# robot_balance.net
KiCad netlist of a schematic drawn in EAGLE
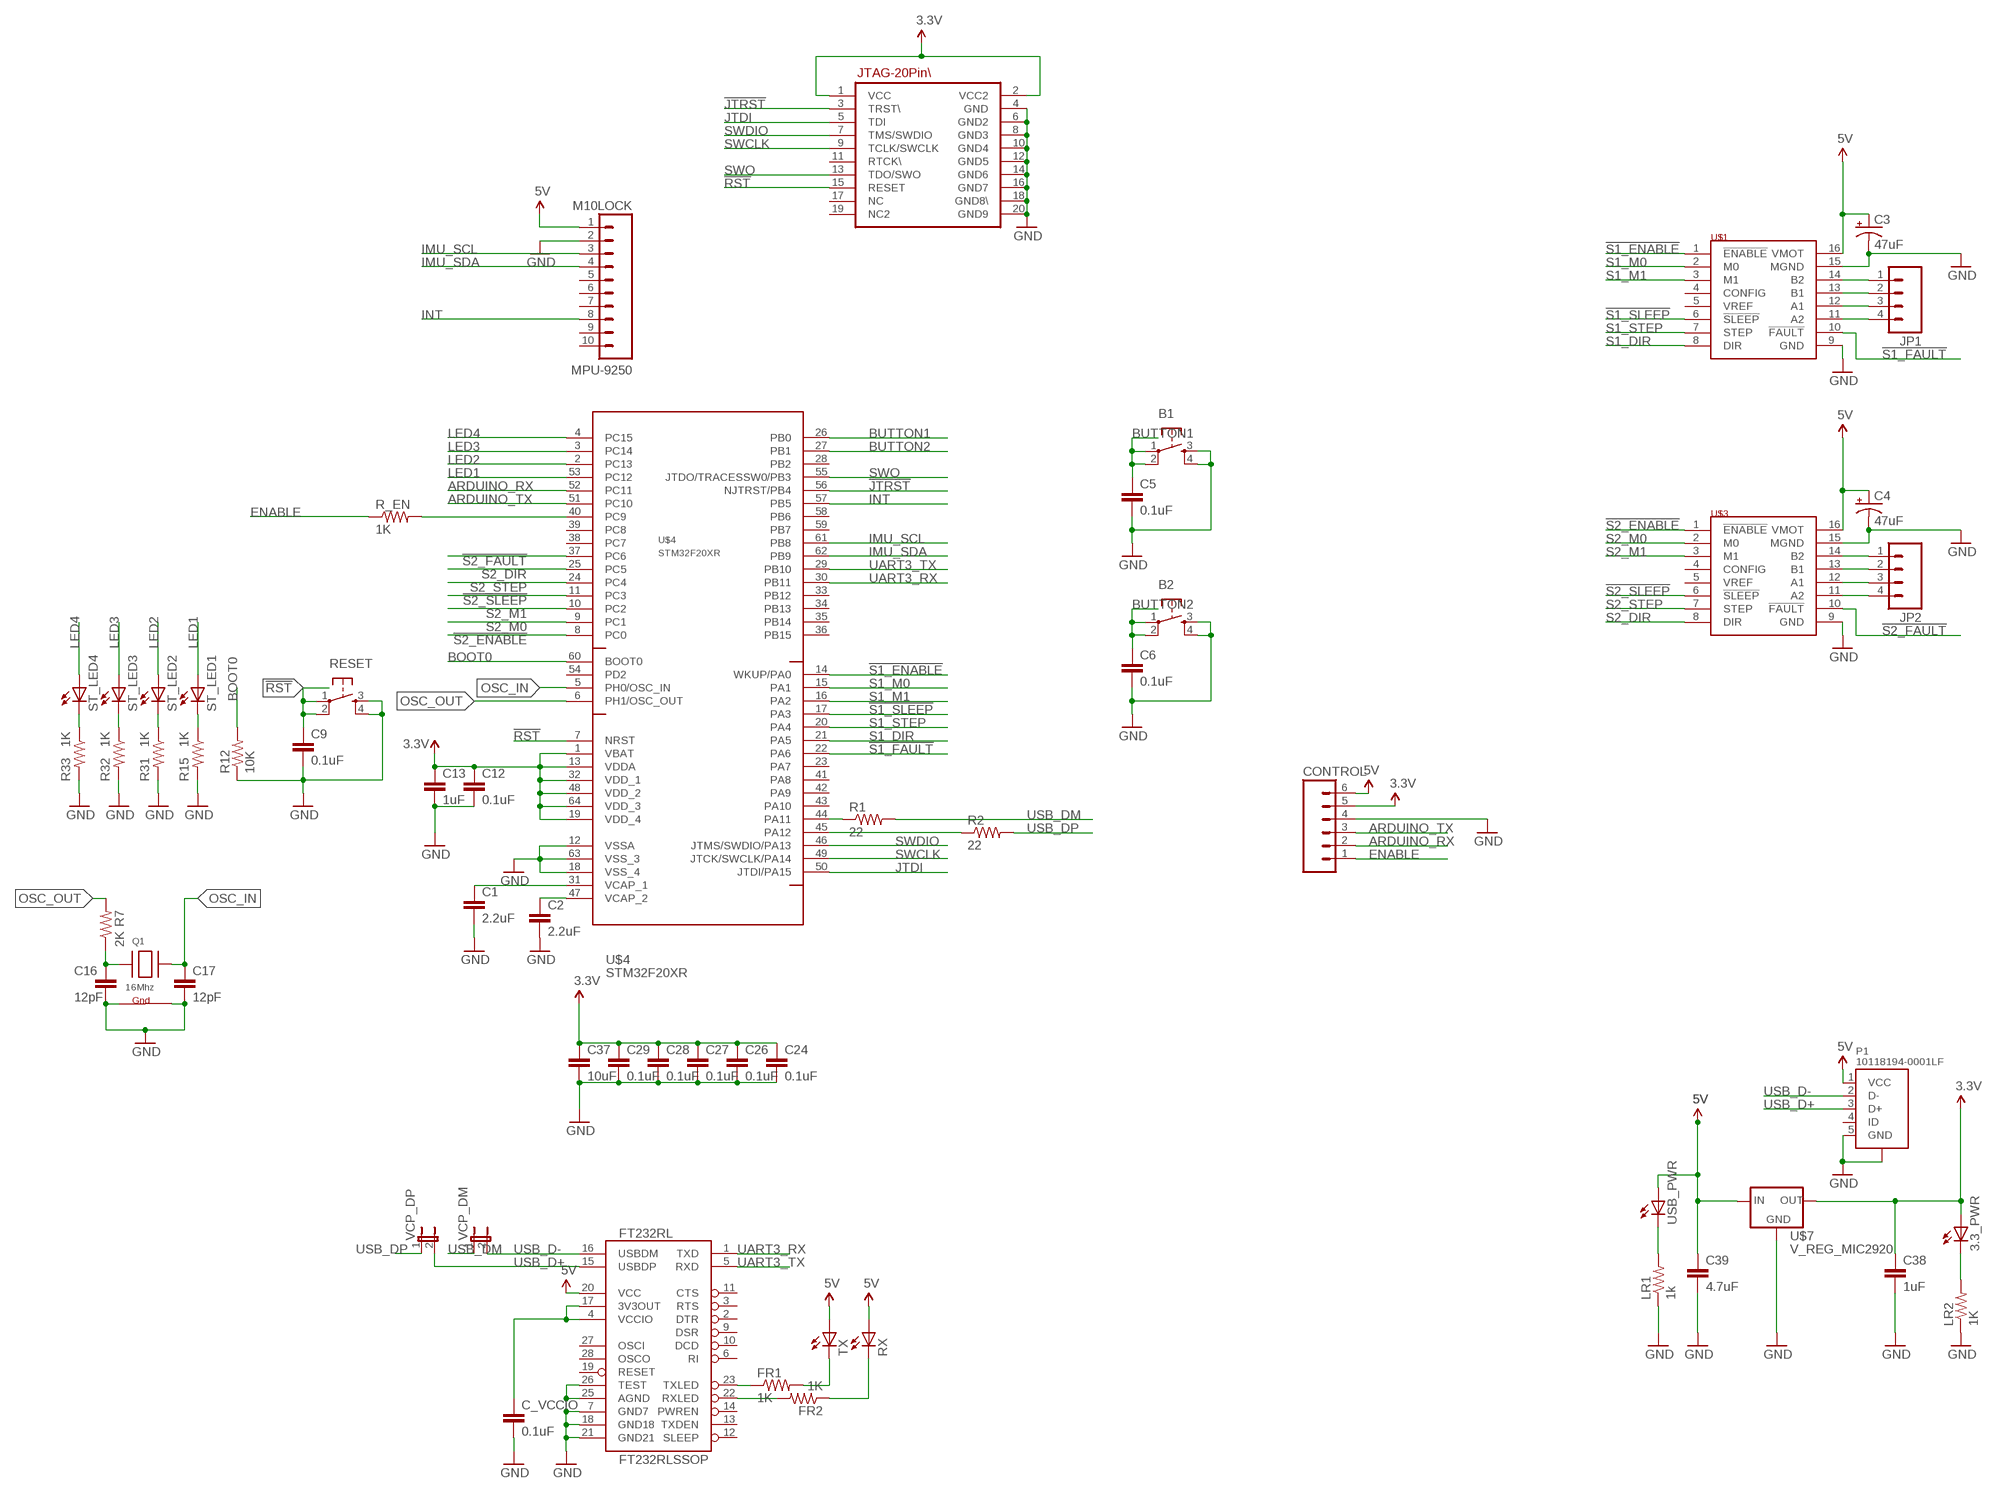
[diagram p0: schematic, sheet 1]

(export (version "E")
  (design (tool "Eeschema 10.0.6"))
  (components
    (comp (ref "3.3_PWR")
      (value "LEDCHIPLED_0805")
      (footprint "eagle-import:CHIPLED_0805")
      (libsource (lib "eagle-import") (part "LEDCHIPLED_0805"))
    )
    (comp (ref "B1")
      (value "TAC_SWITCHSMD")
      (footprint "eagle-import:TACTILE-SWITCH-SMD")
      (libsource (lib "eagle-import") (part "TAC_SWITCHSMD"))
    )
    (comp (ref "B2")
      (value "TAC_SWITCHSMD")
      (footprint "eagle-import:TACTILE-SWITCH-SMD")
      (libsource (lib "eagle-import") (part "TAC_SWITCHSMD"))
    )
    (comp (ref "C1")
      (value "2.2uF")
      (footprint "eagle-import:0805")
      (libsource (lib "eagle-import") (part "2.2UF-25V-+80/-20(0805)"))
    )
    (comp (ref "C2")
      (value "2.2uF")
      (footprint "eagle-import:0805")
      (libsource (lib "eagle-import") (part "2.2UF-25V-+80/-20(0805)"))
    )
    (comp (ref "C3")
      (value "47uF")
      (footprint "eagle-import:EIA3528")
      (libsource (lib "eagle-import") (part "47UF-10V-10%(TANT)"))
    )
    (comp (ref "C4")
      (value "47uF")
      (footprint "eagle-import:EIA3528")
      (libsource (lib "eagle-import") (part "47UF-10V-10%(TANT)"))
    )
    (comp (ref "C5")
      (value "0.1uF")
      (footprint "eagle-import:0805")
      (libsource (lib "eagle-import") (part "2.2UF-25V-+80/-20(0805)"))
    )
    (comp (ref "C6")
      (value "0.1uF")
      (footprint "eagle-import:0805")
      (libsource (lib "eagle-import") (part "2.2UF-25V-+80/-20(0805)"))
    )
    (comp (ref "C9")
      (value "0.1uF")
      (footprint "eagle-import:0805")
      (libsource (lib "eagle-import") (part "2.2UF-25V-+80/-20(0805)"))
    )
    (comp (ref "C12")
      (value "0.1uF")
      (footprint "eagle-import:0805")
      (libsource (lib "eagle-import") (part "2.2UF-25V-+80/-20(0805)"))
    )
    (comp (ref "C13")
      (value "1uF")
      (footprint "eagle-import:0805")
      (libsource (lib "eagle-import") (part "2.2UF-25V-+80/-20(0805)"))
    )
    (comp (ref "C16")
      (value "12pF")
      (footprint "eagle-import:0805")
      (libsource (lib "eagle-import") (part "CAP0805"))
    )
    (comp (ref "C17")
      (value "12pF")
      (footprint "eagle-import:0805")
      (libsource (lib "eagle-import") (part "CAP0805"))
    )
    (comp (ref "C24")
      (value "0.1uF")
      (footprint "eagle-import:0805")
      (libsource (lib "eagle-import") (part "2.2UF-25V-+80/-20(0805)"))
    )
    (comp (ref "C26")
      (value "0.1uF")
      (footprint "eagle-import:0805")
      (libsource (lib "eagle-import") (part "2.2UF-25V-+80/-20(0805)"))
    )
    (comp (ref "C27")
      (value "0.1uF")
      (footprint "eagle-import:0805")
      (libsource (lib "eagle-import") (part "2.2UF-25V-+80/-20(0805)"))
    )
    (comp (ref "C28")
      (value "0.1uF")
      (footprint "eagle-import:0805")
      (libsource (lib "eagle-import") (part "2.2UF-25V-+80/-20(0805)"))
    )
    (comp (ref "C29")
      (value "0.1uF")
      (footprint "eagle-import:0805")
      (libsource (lib "eagle-import") (part "2.2UF-25V-+80/-20(0805)"))
    )
    (comp (ref "C37")
      (value "10uF")
      (footprint "eagle-import:0805")
      (libsource (lib "eagle-import") (part "2.2UF-25V-+80/-20(0805)"))
    )
    (comp (ref "C38")
      (value "1uF")
      (footprint "eagle-import:0805")
      (libsource (lib "eagle-import") (part "22UF-6.3V-20%(0805)"))
    )
    (comp (ref "C39")
      (value "4.7uF")
      (footprint "eagle-import:0805")
      (libsource (lib "eagle-import") (part "22UF-6.3V-20%(0805)"))
    )
    (comp (ref "CONTROL")
      (value "M06POLAR_LOCK")
      (footprint "eagle-import:MOLEX-1X6_LOCK")
      (libsource (lib "eagle-import") (part "M06POLAR_LOCK"))
    )
    (comp (ref "C_VCCIO")
      (value "0.1uF")
      (footprint "eagle-import:0603-CAP")
      (libsource (lib "eagle-import") (part "CAP0603-CAP"))
    )
    (comp (ref "FR1")
      (value "1K")
      (footprint "eagle-import:0603-RES")
      (libsource (lib "eagle-import") (part "RESISTOR0603-RES"))
    )
    (comp (ref "FR2")
      (value "1K")
      (footprint "eagle-import:0603-RES")
      (libsource (lib "eagle-import") (part "RESISTOR0603-RES"))
    )
    (comp (ref "FT232RL")
      (value "FT232RLSSOP")
      (footprint "eagle-import:SSOP28DB")
      (libsource (lib "eagle-import") (part "FT232RLSSOP"))
    )
    (comp (ref "JP1")
      (value "M04POLAR_LOCK")
      (footprint "eagle-import:MOLEX-1X4_LOCK")
      (libsource (lib "eagle-import") (part "M04POLAR_LOCK"))
    )
    (comp (ref "JP2")
      (value "M04POLAR_LOCK")
      (footprint "eagle-import:MOLEX-1X4_LOCK")
      (libsource (lib "eagle-import") (part "M04POLAR_LOCK"))
    )
    (comp (ref "LR1")
      (value "1k")
      (footprint "eagle-import:0805")
      (libsource (lib "eagle-import") (part "SparkFun-Resistors_RESISTOR0805-RES"))
    )
    (comp (ref "LR2")
      (value "1K")
      (footprint "eagle-import:0805")
      (libsource (lib "eagle-import") (part "SparkFun-Resistors_RESISTOR0805-RES"))
    )
    (comp (ref "MPU-9250")
      (value "M10LOCK")
      (footprint "eagle-import:1X10_LOCK")
      (libsource (lib "eagle-import") (part "M10LOCK"))
    )
    (comp (ref "P1")
      (value "10118194-0001LF")
      (footprint "eagle-import:10118194-0001LF")
      (fields
        (field (name "DISTPARTNO") "609-4618-1-ND")
        (field (name "MANUFACTURER") "FCI")
        (field (name "PARTNO") "GT10040")
      )
      (libsource (lib "eagle-import") (part "10118194-0001LF"))
    )
    (comp (ref "Q1")
      (value "16Mhz")
      (footprint "eagle-import:NX3225")
      (libsource (lib "eagle-import") (part "XTAL-4-3225"))
    )
    (comp (ref "R1")
      (value "22")
      (footprint "eagle-import:0805")
      (libsource (lib "eagle-import") (part "RESISTOR0805-RES"))
    )
    (comp (ref "R2")
      (value "22")
      (footprint "eagle-import:0805")
      (libsource (lib "eagle-import") (part "RESISTOR0805-RES"))
    )
    (comp (ref "R7")
      (value "2K")
      (footprint "eagle-import:0805")
      (libsource (lib "eagle-import") (part "SparkFun-Resistors_RESISTOR0805-RES"))
    )
    (comp (ref "R12")
      (value "10K")
      (footprint "eagle-import:0805")
      (libsource (lib "eagle-import") (part "RESISTOR0805-RES"))
    )
    (comp (ref "R15")
      (value "1K")
      (footprint "eagle-import:0805")
      (libsource (lib "eagle-import") (part "SparkFun-Resistors_RESISTOR0805-RES"))
    )
    (comp (ref "R31")
      (value "1K")
      (footprint "eagle-import:0805")
      (libsource (lib "eagle-import") (part "SparkFun-Resistors_RESISTOR0805-RES"))
    )
    (comp (ref "R32")
      (value "1K")
      (footprint "eagle-import:0805")
      (libsource (lib "eagle-import") (part "SparkFun-Resistors_RESISTOR0805-RES"))
    )
    (comp (ref "R33")
      (value "1K")
      (footprint "eagle-import:0805")
      (libsource (lib "eagle-import") (part "SparkFun-Resistors_RESISTOR0805-RES"))
    )
    (comp (ref "RESET")
      (value "TAC_SWITCHSMD")
      (footprint "eagle-import:TACTILE-SWITCH-SMD")
      (libsource (lib "eagle-import") (part "TAC_SWITCHSMD"))
    )
    (comp (ref "RX")
      (value "LEDCHIPLED_0805")
      (footprint "eagle-import:CHIPLED_0805")
      (libsource (lib "eagle-import") (part "LEDCHIPLED_0805"))
    )
    (comp (ref "R_EN")
      (value "1K")
      (footprint "eagle-import:0603-RES")
      (libsource (lib "eagle-import") (part "RESISTOR0603-RES"))
    )
    (comp (ref "ST_LED1")
      (value "LEDCHIPLED_0805")
      (footprint "eagle-import:CHIPLED_0805")
      (libsource (lib "eagle-import") (part "LEDCHIPLED_0805"))
    )
    (comp (ref "ST_LED2")
      (value "LEDCHIPLED_0805")
      (footprint "eagle-import:CHIPLED_0805")
      (libsource (lib "eagle-import") (part "LEDCHIPLED_0805"))
    )
    (comp (ref "ST_LED3")
      (value "LEDCHIPLED_0805")
      (footprint "eagle-import:CHIPLED_0805")
      (libsource (lib "eagle-import") (part "LEDCHIPLED_0805"))
    )
    (comp (ref "ST_LED4")
      (value "LEDCHIPLED_0805")
      (footprint "eagle-import:CHIPLED_0805")
      (libsource (lib "eagle-import") (part "LEDCHIPLED_0805"))
    )
    (comp (ref "TX")
      (value "LEDCHIPLED_0805")
      (footprint "eagle-import:CHIPLED_0805")
      (libsource (lib "eagle-import") (part "LEDCHIPLED_0805"))
    )
    (comp (ref "U$1")
      (value "POLOLU_DRV8834")
      (footprint "eagle-import:POLOLU_DRV8834")
      (libsource (lib "eagle-import") (part "POLOLU_DRV8834"))
    )
    (comp (ref "U$2")
      (value "JTAG_20PIN")
      (footprint "eagle-import:2X10")
      (libsource (lib "eagle-import") (part "JTAG_20PIN"))
    )
    (comp (ref "U$3")
      (value "POLOLU_DRV8834")
      (footprint "eagle-import:POLOLU_DRV8834")
      (libsource (lib "eagle-import") (part "POLOLU_DRV8834"))
    )
    (comp (ref "U$4")
      (value "STM32F20XR")
      (footprint "eagle-import:LQFP64")
      (libsource (lib "eagle-import") (part "STM32F20XR"))
    )
    (comp (ref "U$7")
      (value "V_REG_MIC2920")
      (footprint "eagle-import:SOT223")
      (libsource (lib "eagle-import") (part "V_REG_MIC2920"))
    )
    (comp (ref "USB_PWR")
      (value "LEDCHIP-LED0805")
      (footprint "eagle-import:CHIP-LED0805")
      (libsource (lib "eagle-import") (part "LEDCHIP-LED0805"))
    )
    (comp (ref "VCP_DM")
      (value "JUMPER-2SMD-NO")
      (footprint "eagle-import:SJ_2S-NO")
      (libsource (lib "eagle-import") (part "JUMPER-2SMD-NO"))
    )
    (comp (ref "VCP_DP")
      (value "JUMPER-2SMD-NO")
      (footprint "eagle-import:SJ_2S-NO")
      (libsource (lib "eagle-import") (part "JUMPER-2SMD-NO"))
    )
  )
  (nets
    (net (code "1") (name "/ARDUINO_RX") (class "Default")
      (node (ref "CONTROL") (pin "2") (pinfunction "2_2") (pintype "passive"))
      (node (ref "U$4") (pin "52") (pinfunction "PC11_52") (pintype "bidirectional"))
    )
    (net (code "2") (name "/ARDUINO_TX") (class "Default")
      (node (ref "CONTROL") (pin "3") (pinfunction "3_3") (pintype "passive"))
      (node (ref "U$4") (pin "51") (pinfunction "PC10_51") (pintype "bidirectional"))
    )
    (net (code "3") (name "/BOOT0") (class "Default")
      (node (ref "R12") (pin "2") (pinfunction "2_2") (pintype "passive"))
      (node (ref "U$4") (pin "60") (pinfunction "BOOT0_60") (pintype "bidirectional"))
    )
    (net (code "4") (name "/BUTTON1") (class "Default")
      (node (ref "B1") (pin "1") (pinfunction "1_1") (pintype "passive"))
      (node (ref "B1") (pin "2") (pinfunction "2_2") (pintype "passive"))
      (node (ref "C5") (pin "1") (pinfunction "1_1") (pintype "passive"))
      (node (ref "U$4") (pin "26") (pinfunction "PB0_26") (pintype "bidirectional"))
    )
    (net (code "5") (name "/BUTTON2") (class "Default")
      (node (ref "B2") (pin "1") (pinfunction "1_1") (pintype "passive"))
      (node (ref "B2") (pin "2") (pinfunction "2_2") (pintype "passive"))
      (node (ref "C6") (pin "1") (pinfunction "1_1") (pintype "passive"))
      (node (ref "U$4") (pin "27") (pinfunction "PB1_27") (pintype "bidirectional"))
    )
    (net (code "6") (name "/ENABLE") (class "Default")
      (node (ref "CONTROL") (pin "1") (pinfunction "1_1") (pintype "passive"))
      (node (ref "R_EN") (pin "1") (pinfunction "1_1") (pintype "passive"))
    )
    (net (code "7") (name "/IMU_SCL") (class "Default")
      (node (ref "MPU-9250") (pin "3") (pinfunction "3_3") (pintype "passive"))
      (node (ref "U$4") (pin "61") (pinfunction "PB8_61") (pintype "bidirectional"))
    )
    (net (code "8") (name "/IMU_SDA") (class "Default")
      (node (ref "MPU-9250") (pin "4") (pinfunction "4_4") (pintype "passive"))
      (node (ref "U$4") (pin "62") (pinfunction "PB9_62") (pintype "bidirectional"))
    )
    (net (code "9") (name "/INT") (class "Default")
      (node (ref "MPU-9250") (pin "8") (pinfunction "8_8") (pintype "passive"))
      (node (ref "U$4") (pin "57") (pinfunction "PB5_57") (pintype "bidirectional"))
    )
    (net (code "10") (name "/JTDI") (class "Default")
      (node (ref "U$2") (pin "5") (pinfunction "TDI_5") (pintype "bidirectional"))
      (node (ref "U$4") (pin "50") (pinfunction "JTDI/PA15_50") (pintype "bidirectional"))
    )
    (net (code "11") (name "/LED1") (class "Default")
      (node (ref "ST_LED1") (pin "A") (pinfunction "A_A") (pintype "passive"))
      (node (ref "U$4") (pin "53") (pinfunction "PC12_53") (pintype "bidirectional"))
    )
    (net (code "12") (name "/LED2") (class "Default")
      (node (ref "ST_LED2") (pin "A") (pinfunction "A_A") (pintype "passive"))
      (node (ref "U$4") (pin "2") (pinfunction "PC13_2") (pintype "bidirectional"))
    )
    (net (code "13") (name "/LED3") (class "Default")
      (node (ref "ST_LED3") (pin "A") (pinfunction "A_A") (pintype "passive"))
      (node (ref "U$4") (pin "3") (pinfunction "PC14_3") (pintype "bidirectional"))
    )
    (net (code "14") (name "/LED4") (class "Default")
      (node (ref "ST_LED4") (pin "A") (pinfunction "A_A") (pintype "passive"))
      (node (ref "U$4") (pin "4") (pinfunction "PC15_4") (pintype "bidirectional"))
    )
    (net (code "15") (name "/S1_DIR") (class "Default")
      (node (ref "U$1") (pin "8") (pinfunction "DIR_8") (pintype "bidirectional"))
      (node (ref "U$4") (pin "21") (pinfunction "PA5_21") (pintype "bidirectional"))
    )
    (net (code "16") (name "/S1_M0") (class "Default")
      (node (ref "U$1") (pin "2") (pinfunction "M0_2") (pintype "bidirectional"))
      (node (ref "U$4") (pin "15") (pinfunction "PA1_15") (pintype "bidirectional"))
    )
    (net (code "17") (name "/S1_M1") (class "Default")
      (node (ref "U$1") (pin "3") (pinfunction "M1_3") (pintype "bidirectional"))
      (node (ref "U$4") (pin "16") (pinfunction "PA2_16") (pintype "bidirectional"))
    )
    (net (code "18") (name "/S1_STEP") (class "Default")
      (node (ref "U$1") (pin "7") (pinfunction "STEP_7") (pintype "bidirectional"))
      (node (ref "U$4") (pin "20") (pinfunction "PA4_20") (pintype "bidirectional"))
    )
    (net (code "19") (name "/S2_DIR") (class "Default")
      (node (ref "U$3") (pin "8") (pinfunction "DIR_8") (pintype "bidirectional"))
      (node (ref "U$4") (pin "25") (pinfunction "PC5_25") (pintype "bidirectional"))
    )
    (net (code "20") (name "/S2_M0") (class "Default")
      (node (ref "U$3") (pin "2") (pinfunction "M0_2") (pintype "bidirectional"))
      (node (ref "U$4") (pin "9") (pinfunction "PC1_9") (pintype "bidirectional"))
    )
    (net (code "21") (name "/S2_M1") (class "Default")
      (node (ref "U$3") (pin "3") (pinfunction "M1_3") (pintype "bidirectional"))
      (node (ref "U$4") (pin "10") (pinfunction "PC2_10") (pintype "bidirectional"))
    )
    (net (code "22") (name "/S2_STEP") (class "Default")
      (node (ref "U$3") (pin "7") (pinfunction "STEP_7") (pintype "bidirectional"))
      (node (ref "U$4") (pin "24") (pinfunction "PC4_24") (pintype "bidirectional"))
    )
    (net (code "23") (name "/SWCLK") (class "Default")
      (node (ref "U$2") (pin "9") (pinfunction "TCLK/SWCLK_9") (pintype "bidirectional"))
      (node (ref "U$4") (pin "49") (pinfunction "JTCK/SWCLK/PA14_49") (pintype "bidirectional"))
    )
    (net (code "24") (name "/SWDIO") (class "Default")
      (node (ref "U$2") (pin "7") (pinfunction "TMS/SWDIO_7") (pintype "bidirectional"))
      (node (ref "U$4") (pin "46") (pinfunction "JTMS/SWDIO/PA13_46") (pintype "bidirectional"))
    )
    (net (code "25") (name "/SWO") (class "Default")
      (node (ref "U$2") (pin "13") (pinfunction "TDO/SWO_13") (pintype "bidirectional"))
      (node (ref "U$4") (pin "55") (pinfunction "JTDO/TRACESSW0/PB3_55") (pintype "bidirectional"))
    )
    (net (code "26") (name "/UART3_RX") (class "Default")
      (node (ref "FT232RL") (pin "1") (pinfunction "TXD_1") (pintype "output"))
      (node (ref "U$4") (pin "30") (pinfunction "PB11_30") (pintype "bidirectional"))
    )
    (net (code "27") (name "/UART3_TX") (class "Default")
      (node (ref "FT232RL") (pin "5") (pinfunction "RXD_5") (pintype "input"))
      (node (ref "U$4") (pin "29") (pinfunction "PB10_29") (pintype "bidirectional"))
    )
    (net (code "28") (name "/USB_D+") (class "Default")
      (node (ref "FT232RL") (pin "15") (pinfunction "USBDP_15") (pintype "bidirectional"))
      (node (ref "P1") (pin "3") (pinfunction "D+_3") (pintype "passive"))
      (node (ref "VCP_DP") (pin "2") (pinfunction "2_2") (pintype "passive"))
    )
    (net (code "29") (name "/USB_D-") (class "Default")
      (node (ref "FT232RL") (pin "16") (pinfunction "USBDM_16") (pintype "bidirectional"))
      (node (ref "P1") (pin "2") (pinfunction "D-_2") (pintype "passive"))
      (node (ref "VCP_DM") (pin "2") (pinfunction "2_2") (pintype "passive"))
    )
    (net (code "30") (name "/USB_DM") (class "Default")
      (node (ref "R1") (pin "2") (pinfunction "2_2") (pintype "passive"))
      (node (ref "VCP_DM") (pin "1") (pinfunction "1_1") (pintype "passive"))
    )
    (net (code "31") (name "/USB_DP") (class "Default")
      (node (ref "R2") (pin "2") (pinfunction "2_2") (pintype "passive"))
      (node (ref "VCP_DP") (pin "1") (pinfunction "1_1") (pintype "passive"))
    )
    (net (code "32") (name "/~{JTRST}") (class "Default")
      (node (ref "U$2") (pin "3") (pinfunction "TRST\\_3") (pintype "bidirectional"))
      (node (ref "U$4") (pin "56") (pinfunction "NJTRST/PB4_56") (pintype "bidirectional"))
    )
    (net (code "33") (name "/~{RST}") (class "Default")
      (node (ref "C9") (pin "1") (pinfunction "1_1") (pintype "passive"))
      (node (ref "RESET") (pin "1") (pinfunction "1_1") (pintype "passive"))
      (node (ref "RESET") (pin "2") (pinfunction "2_2") (pintype "passive"))
      (node (ref "U$2") (pin "15") (pinfunction "RESET_15") (pintype "bidirectional"))
      (node (ref "U$4") (pin "7") (pinfunction "NRST_7") (pintype "power_in"))
    )
    (net (code "34") (name "/~{S1_ENABLE}") (class "Default")
      (node (ref "U$1") (pin "1") (pinfunction "~{ENABLE}_1") (pintype "bidirectional"))
      (node (ref "U$4") (pin "14") (pinfunction "WKUP/PA0_14") (pintype "bidirectional"))
    )
    (net (code "35") (name "/~{S1_FAULT}") (class "Default")
      (node (ref "U$1") (pin "10") (pinfunction "~{FAULT}_10") (pintype "bidirectional"))
      (node (ref "U$4") (pin "22") (pinfunction "PA6_22") (pintype "bidirectional"))
    )
    (net (code "36") (name "/~{S1_SLEEP}") (class "Default")
      (node (ref "U$1") (pin "6") (pinfunction "~{SLEEP}_6") (pintype "bidirectional"))
      (node (ref "U$4") (pin "17") (pinfunction "PA3_17") (pintype "bidirectional"))
    )
    (net (code "37") (name "/~{S2_ENABLE}") (class "Default")
      (node (ref "U$3") (pin "1") (pinfunction "~{ENABLE}_1") (pintype "bidirectional"))
      (node (ref "U$4") (pin "8") (pinfunction "PC0_8") (pintype "bidirectional"))
    )
    (net (code "38") (name "/~{S2_FAULT}") (class "Default")
      (node (ref "U$3") (pin "10") (pinfunction "~{FAULT}_10") (pintype "bidirectional"))
      (node (ref "U$4") (pin "37") (pinfunction "PC6_37") (pintype "bidirectional"))
    )
    (net (code "39") (name "/~{S2_SLEEP}") (class "Default")
      (node (ref "U$3") (pin "6") (pinfunction "~{SLEEP}_6") (pintype "bidirectional"))
      (node (ref "U$4") (pin "11") (pinfunction "PC3_11") (pintype "bidirectional"))
    )
    (net (code "40") (name "3.3V") (class "Default")
      (node (ref "3.3_PWR") (pin "A") (pinfunction "A_A") (pintype "passive"))
      (node (ref "C12") (pin "1") (pinfunction "1_1") (pintype "passive"))
      (node (ref "C13") (pin "1") (pinfunction "1_1") (pintype "passive"))
      (node (ref "C24") (pin "1") (pinfunction "1_1") (pintype "passive"))
      (node (ref "C26") (pin "1") (pinfunction "1_1") (pintype "passive"))
      (node (ref "C27") (pin "1") (pinfunction "1_1") (pintype "passive"))
      (node (ref "C28") (pin "1") (pinfunction "1_1") (pintype "passive"))
      (node (ref "C29") (pin "1") (pinfunction "1_1") (pintype "passive"))
      (node (ref "C37") (pin "1") (pinfunction "1_1") (pintype "passive"))
      (node (ref "C38") (pin "1") (pinfunction "1_1") (pintype "passive"))
      (node (ref "CONTROL") (pin "5") (pinfunction "5_5") (pintype "passive"))
      (node (ref "U$2") (pin "1") (pinfunction "VCC_1") (pintype "bidirectional"))
      (node (ref "U$2") (pin "2") (pinfunction "VCC2_2") (pintype "bidirectional"))
      (node (ref "U$4") (pin "1") (pinfunction "VBAT_1") (pintype "power_in"))
      (node (ref "U$4") (pin "13") (pinfunction "VDDA_13") (pintype "power_in"))
      (node (ref "U$4") (pin "19") (pinfunction "VDD_4_19") (pintype "power_in"))
      (node (ref "U$4") (pin "32") (pinfunction "VDD_1_32") (pintype "power_in"))
      (node (ref "U$4") (pin "48") (pinfunction "VDD_2_48") (pintype "power_in"))
      (node (ref "U$4") (pin "64") (pinfunction "VDD_3_64") (pintype "power_in"))
      (node (ref "U$7") (pin "3") (pinfunction "OUT_3") (pintype "output"))
    )
    (net (code "41") (name "5V") (class "Default")
      (node (ref "C3") (pin "A") (pinfunction "+_A") (pintype "passive"))
      (node (ref "C39") (pin "1") (pinfunction "1_1") (pintype "passive"))
      (node (ref "C4") (pin "A") (pinfunction "+_A") (pintype "passive"))
      (node (ref "CONTROL") (pin "6") (pinfunction "6_6") (pintype "passive"))
      (node (ref "FT232RL") (pin "20") (pinfunction "VCC_20") (pintype "power_in"))
      (node (ref "MPU-9250") (pin "1") (pinfunction "1_1") (pintype "passive"))
      (node (ref "P1") (pin "1") (pinfunction "VCC_1") (pintype "passive"))
      (node (ref "RX") (pin "A") (pinfunction "A_A") (pintype "passive"))
      (node (ref "TX") (pin "A") (pinfunction "A_A") (pintype "passive"))
      (node (ref "U$1") (pin "16") (pinfunction "VMOT_16") (pintype "power_in"))
      (node (ref "U$3") (pin "16") (pinfunction "VMOT_16") (pintype "power_in"))
      (node (ref "U$7") (pin "1") (pinfunction "IN_1") (pintype "input"))
      (node (ref "USB_PWR") (pin "A") (pinfunction "A_A") (pintype "passive"))
    )
    (net (code "42") (name "GND") (class "Default")
      (node (ref "B1") (pin "3") (pinfunction "3_3") (pintype "passive"))
      (node (ref "B1") (pin "4") (pinfunction "4_4") (pintype "passive"))
      (node (ref "B2") (pin "3") (pinfunction "3_3") (pintype "passive"))
      (node (ref "B2") (pin "4") (pinfunction "4_4") (pintype "passive"))
      (node (ref "C1") (pin "2") (pinfunction "2_2") (pintype "passive"))
      (node (ref "C12") (pin "2") (pinfunction "2_2") (pintype "passive"))
      (node (ref "C13") (pin "2") (pinfunction "2_2") (pintype "passive"))
      (node (ref "C16") (pin "2") (pinfunction "2_2") (pintype "passive"))
      (node (ref "C17") (pin "2") (pinfunction "2_2") (pintype "passive"))
      (node (ref "C2") (pin "2") (pinfunction "2_2") (pintype "passive"))
      (node (ref "C24") (pin "2") (pinfunction "2_2") (pintype "passive"))
      (node (ref "C26") (pin "2") (pinfunction "2_2") (pintype "passive"))
      (node (ref "C27") (pin "2") (pinfunction "2_2") (pintype "passive"))
      (node (ref "C28") (pin "2") (pinfunction "2_2") (pintype "passive"))
      (node (ref "C29") (pin "2") (pinfunction "2_2") (pintype "passive"))
      (node (ref "C3") (pin "C") (pinfunction "-_C") (pintype "passive"))
      (node (ref "C37") (pin "2") (pinfunction "2_2") (pintype "passive"))
      (node (ref "C38") (pin "2") (pinfunction "2_2") (pintype "passive"))
      (node (ref "C39") (pin "2") (pinfunction "2_2") (pintype "passive"))
      (node (ref "C4") (pin "C") (pinfunction "-_C") (pintype "passive"))
      (node (ref "C5") (pin "2") (pinfunction "2_2") (pintype "passive"))
      (node (ref "C6") (pin "2") (pinfunction "2_2") (pintype "passive"))
      (node (ref "C9") (pin "2") (pinfunction "2_2") (pintype "passive"))
      (node (ref "CONTROL") (pin "4") (pinfunction "4_4") (pintype "passive"))
      (node (ref "C_VCCIO") (pin "2") (pinfunction "2_2") (pintype "passive"))
      (node (ref "FT232RL") (pin "18") (pinfunction "GND18_18") (pintype "power_in"))
      (node (ref "FT232RL") (pin "21") (pinfunction "GND21_21") (pintype "power_in"))
      (node (ref "FT232RL") (pin "25") (pinfunction "AGND_25") (pintype "power_in"))
      (node (ref "FT232RL") (pin "26") (pinfunction "TEST_26") (pintype "input"))
      (node (ref "FT232RL") (pin "7") (pinfunction "GND7_7") (pintype "power_in"))
      (node (ref "LR1") (pin "1") (pinfunction "1_1") (pintype "passive"))
      (node (ref "LR2") (pin "1") (pinfunction "1_1") (pintype "passive"))
      (node (ref "MPU-9250") (pin "2") (pinfunction "2_2") (pintype "passive"))
      (node (ref "P1") (pin "5") (pinfunction "GND_5") (pintype "passive"))
      (node (ref "P1") (pin "M1") (pinfunction "SHIELD_M1") (pintype "passive"))
      (node (ref "P1") (pin "M2") (pinfunction "SHIELD_M2") (pintype "passive"))
      (node (ref "P1") (pin "M3") (pinfunction "SHIELD_M3") (pintype "passive"))
      (node (ref "P1") (pin "M4") (pinfunction "SHIELD_M4") (pintype "passive"))
      (node (ref "Q1") (pin "2") (pinfunction "G2_2") (pintype "power_in"))
      (node (ref "Q1") (pin "4") (pinfunction "G1_4") (pintype "power_in"))
      (node (ref "R12") (pin "1") (pinfunction "1_1") (pintype "passive"))
      (node (ref "R15") (pin "2") (pinfunction "2_2") (pintype "passive"))
      (node (ref "R31") (pin "2") (pinfunction "2_2") (pintype "passive"))
      (node (ref "R32") (pin "2") (pinfunction "2_2") (pintype "passive"))
      (node (ref "R33") (pin "2") (pinfunction "2_2") (pintype "passive"))
      (node (ref "RESET") (pin "3") (pinfunction "3_3") (pintype "passive"))
      (node (ref "RESET") (pin "4") (pinfunction "4_4") (pintype "passive"))
      (node (ref "U$1") (pin "15") (pinfunction "MGND_15") (pintype "power_in"))
      (node (ref "U$1") (pin "9") (pinfunction "GND_9") (pintype "power_in"))
      (node (ref "U$2") (pin "10") (pinfunction "GND4_10") (pintype "bidirectional"))
      (node (ref "U$2") (pin "12") (pinfunction "GND5_12") (pintype "bidirectional"))
      (node (ref "U$2") (pin "14") (pinfunction "GND6_14") (pintype "bidirectional"))
      (node (ref "U$2") (pin "16") (pinfunction "GND7_16") (pintype "bidirectional"))
      (node (ref "U$2") (pin "18") (pinfunction "GND8\\_18") (pintype "bidirectional"))
      (node (ref "U$2") (pin "20") (pinfunction "GND9_20") (pintype "bidirectional"))
      (node (ref "U$2") (pin "4") (pinfunction "GND_4") (pintype "bidirectional"))
      (node (ref "U$2") (pin "6") (pinfunction "GND2_6") (pintype "bidirectional"))
      (node (ref "U$2") (pin "8") (pinfunction "GND3_8") (pintype "bidirectional"))
      (node (ref "U$3") (pin "15") (pinfunction "MGND_15") (pintype "power_in"))
      (node (ref "U$3") (pin "9") (pinfunction "GND_9") (pintype "power_in"))
      (node (ref "U$4") (pin "12") (pinfunction "VSSA_12") (pintype "power_in"))
      (node (ref "U$4") (pin "18") (pinfunction "VSS_4_18") (pintype "power_in"))
      (node (ref "U$4") (pin "63") (pinfunction "VSS_3_63") (pintype "power_in"))
      (node (ref "U$7") (pin "2") (pinfunction "GND_2") (pintype "input"))
    )
    (net (code "43") (name "Net-(3.3_PWR-PadC)") (class "Default")
      (node (ref "3.3_PWR") (pin "C") (pinfunction "C_C") (pintype "passive"))
      (node (ref "LR2") (pin "2") (pinfunction "2_2") (pintype "passive"))
    )
    (net (code "44") (name "Net-(FR1-Pad2)") (class "Default")
      (node (ref "FR1") (pin "2") (pinfunction "2_2") (pintype "passive"))
      (node (ref "TX") (pin "C") (pinfunction "C_C") (pintype "passive"))
    )
    (net (code "45") (name "Net-(FR2-Pad1)") (class "Default")
      (node (ref "FR2") (pin "1") (pinfunction "1_1") (pintype "passive"))
      (node (ref "RX") (pin "C") (pinfunction "C_C") (pintype "passive"))
    )
    (net (code "46") (name "Net-(FT232RL-3V3OUT)") (class "Default")
      (node (ref "C_VCCIO") (pin "1") (pinfunction "1_1") (pintype "passive"))
      (node (ref "FT232RL") (pin "17") (pinfunction "3V3OUT_17") (pintype "output"))
      (node (ref "FT232RL") (pin "4") (pinfunction "VCCIO_4") (pintype "power_in"))
    )
    (net (code "47") (name "Net-(FT232RL-RXLED)") (class "Default")
      (node (ref "FR2") (pin "2") (pinfunction "2_2") (pintype "passive"))
      (node (ref "FT232RL") (pin "22") (pinfunction "RXLED_22") (pintype "input"))
    )
    (net (code "48") (name "Net-(FT232RL-TXLED)") (class "Default")
      (node (ref "FR1") (pin "1") (pinfunction "1_1") (pintype "passive"))
      (node (ref "FT232RL") (pin "23") (pinfunction "TXLED_23") (pintype "input"))
    )
    (net (code "49") (name "Net-(LR1-Pad2)") (class "Default")
      (node (ref "LR1") (pin "2") (pinfunction "2_2") (pintype "passive"))
      (node (ref "USB_PWR") (pin "C") (pinfunction "C_C") (pintype "passive"))
    )
    (net (code "50") (name "Net-(Q1-X1)") (class "Default")
      (node (ref "C16") (pin "1") (pinfunction "1_1") (pintype "passive"))
      (node (ref "Q1") (pin "1") (pinfunction "X1_1") (pintype "bidirectional"))
      (node (ref "R7") (pin "1") (pinfunction "1_1") (pintype "passive"))
    )
    (net (code "51") (name "Net-(R15-Pad1)") (class "Default")
      (node (ref "R15") (pin "1") (pinfunction "1_1") (pintype "passive"))
      (node (ref "ST_LED1") (pin "C") (pinfunction "C_C") (pintype "passive"))
    )
    (net (code "52") (name "Net-(R31-Pad1)") (class "Default")
      (node (ref "R31") (pin "1") (pinfunction "1_1") (pintype "passive"))
      (node (ref "ST_LED2") (pin "C") (pinfunction "C_C") (pintype "passive"))
    )
    (net (code "53") (name "Net-(R32-Pad1)") (class "Default")
      (node (ref "R32") (pin "1") (pinfunction "1_1") (pintype "passive"))
      (node (ref "ST_LED3") (pin "C") (pinfunction "C_C") (pintype "passive"))
    )
    (net (code "54") (name "Net-(R33-Pad1)") (class "Default")
      (node (ref "R33") (pin "1") (pinfunction "1_1") (pintype "passive"))
      (node (ref "ST_LED4") (pin "C") (pinfunction "C_C") (pintype "passive"))
    )
    (net (code "55") (name "Net-(U$1-A1)") (class "Default")
      (node (ref "JP1") (pin "3") (pinfunction "3_3") (pintype "passive"))
      (node (ref "U$1") (pin "12") (pinfunction "A1_12") (pintype "bidirectional"))
    )
    (net (code "56") (name "Net-(U$1-A2)") (class "Default")
      (node (ref "JP1") (pin "4") (pinfunction "4_4") (pintype "passive"))
      (node (ref "U$1") (pin "11") (pinfunction "A2_11") (pintype "bidirectional"))
    )
    (net (code "57") (name "Net-(U$1-B1)") (class "Default")
      (node (ref "JP1") (pin "2") (pinfunction "2_2") (pintype "passive"))
      (node (ref "U$1") (pin "13") (pinfunction "B1_13") (pintype "bidirectional"))
    )
    (net (code "58") (name "Net-(U$1-B2)") (class "Default")
      (node (ref "JP1") (pin "1") (pinfunction "1_1") (pintype "passive"))
      (node (ref "U$1") (pin "14") (pinfunction "B2_14") (pintype "bidirectional"))
    )
    (net (code "59") (name "Net-(U$3-A1)") (class "Default")
      (node (ref "JP2") (pin "3") (pinfunction "3_3") (pintype "passive"))
      (node (ref "U$3") (pin "12") (pinfunction "A1_12") (pintype "bidirectional"))
    )
    (net (code "60") (name "Net-(U$3-A2)") (class "Default")
      (node (ref "JP2") (pin "4") (pinfunction "4_4") (pintype "passive"))
      (node (ref "U$3") (pin "11") (pinfunction "A2_11") (pintype "bidirectional"))
    )
    (net (code "61") (name "Net-(U$3-B1)") (class "Default")
      (node (ref "JP2") (pin "2") (pinfunction "2_2") (pintype "passive"))
      (node (ref "U$3") (pin "13") (pinfunction "B1_13") (pintype "bidirectional"))
    )
    (net (code "62") (name "Net-(U$3-B2)") (class "Default")
      (node (ref "JP2") (pin "1") (pinfunction "1_1") (pintype "passive"))
      (node (ref "U$3") (pin "14") (pinfunction "B2_14") (pintype "bidirectional"))
    )
    (net (code "63") (name "Net-(U$4-PA11)") (class "Default")
      (node (ref "R1") (pin "1") (pinfunction "1_1") (pintype "passive"))
      (node (ref "U$4") (pin "44") (pinfunction "PA11_44") (pintype "bidirectional"))
    )
    (net (code "64") (name "Net-(U$4-PA12)") (class "Default")
      (node (ref "R2") (pin "1") (pinfunction "1_1") (pintype "passive"))
      (node (ref "U$4") (pin "45") (pinfunction "PA12_45") (pintype "bidirectional"))
    )
    (net (code "65") (name "Net-(U$4-PC9)") (class "Default")
      (node (ref "R_EN") (pin "2") (pinfunction "2_2") (pintype "passive"))
      (node (ref "U$4") (pin "40") (pinfunction "PC9_40") (pintype "bidirectional"))
    )
    (net (code "66") (name "Net-(U$4-VCAP_1)") (class "Default")
      (node (ref "C1") (pin "1") (pinfunction "1_1") (pintype "passive"))
      (node (ref "U$4") (pin "31") (pinfunction "VCAP_1_31") (pintype "power_in"))
    )
    (net (code "67") (name "Net-(U$4-VCAP_2)") (class "Default")
      (node (ref "C2") (pin "1") (pinfunction "1_1") (pintype "passive"))
      (node (ref "U$4") (pin "47") (pinfunction "VCAP_2_47") (pintype "power_in"))
    )
    (net (code "68") (name "OSC_IN") (class "Default")
      (node (ref "C17") (pin "1") (pinfunction "1_1") (pintype "passive"))
      (node (ref "Q1") (pin "3") (pinfunction "X2_3") (pintype "bidirectional"))
      (node (ref "U$4") (pin "5") (pinfunction "PH0/OSC_IN_5") (pintype "bidirectional"))
    )
    (net (code "69") (name "OSC_OUT") (class "Default")
      (node (ref "R7") (pin "2") (pinfunction "2_2") (pintype "passive"))
      (node (ref "U$4") (pin "6") (pinfunction "PH1/OSC_OUT_6") (pintype "bidirectional"))
    )
    (net (code "70") (name "unconnected-(FT232RL-CTS-Pad11)") (class "Default")
      (node (ref "FT232RL") (pin "11") (pinfunction "CTS_11") (pintype "input"))
    )
    (net (code "71") (name "unconnected-(FT232RL-DCD-Pad10)") (class "Default")
      (node (ref "FT232RL") (pin "10") (pinfunction "DCD_10") (pintype "input"))
    )
    (net (code "72") (name "unconnected-(FT232RL-DSR-Pad9)") (class "Default")
      (node (ref "FT232RL") (pin "9") (pinfunction "DSR_9") (pintype "input"))
    )
    (net (code "73") (name "unconnected-(FT232RL-DTR-Pad2)") (class "Default")
      (node (ref "FT232RL") (pin "2") (pinfunction "DTR_2") (pintype "output"))
    )
    (net (code "74") (name "unconnected-(FT232RL-OSCI-Pad27)") (class "Default")
      (node (ref "FT232RL") (pin "27") (pinfunction "OSCI_27") (pintype "input"))
    )
    (net (code "75") (name "unconnected-(FT232RL-OSCO-Pad28)") (class "Default")
      (node (ref "FT232RL") (pin "28") (pinfunction "OSCO_28") (pintype "output"))
    )
    (net (code "76") (name "unconnected-(FT232RL-PWREN-Pad14)") (class "Default")
      (node (ref "FT232RL") (pin "14") (pinfunction "PWREN_14") (pintype "input"))
    )
    (net (code "77") (name "unconnected-(FT232RL-RESET-Pad19)") (class "Default")
      (node (ref "FT232RL") (pin "19") (pinfunction "RESET_19") (pintype "input"))
    )
    (net (code "78") (name "unconnected-(FT232RL-RI-Pad6)") (class "Default")
      (node (ref "FT232RL") (pin "6") (pinfunction "RI_6") (pintype "input"))
    )
    (net (code "79") (name "unconnected-(FT232RL-RTS-Pad3)") (class "Default")
      (node (ref "FT232RL") (pin "3") (pinfunction "RTS_3") (pintype "output"))
    )
    (net (code "80") (name "unconnected-(FT232RL-SLEEP-Pad12)") (class "Default")
      (node (ref "FT232RL") (pin "12") (pinfunction "SLEEP_12") (pintype "input"))
    )
    (net (code "81") (name "unconnected-(FT232RL-TXDEN-Pad13)") (class "Default")
      (node (ref "FT232RL") (pin "13") (pinfunction "TXDEN_13") (pintype "input"))
    )
    (net (code "82") (name "unconnected-(MPU-9250-Pad5)") (class "Default")
      (node (ref "MPU-9250") (pin "5") (pinfunction "5_5") (pintype "passive"))
    )
    (net (code "83") (name "unconnected-(MPU-9250-Pad6)") (class "Default")
      (node (ref "MPU-9250") (pin "6") (pinfunction "6_6") (pintype "passive"))
    )
    (net (code "84") (name "unconnected-(MPU-9250-Pad7)") (class "Default")
      (node (ref "MPU-9250") (pin "7") (pinfunction "7_7") (pintype "passive"))
    )
    (net (code "85") (name "unconnected-(MPU-9250-Pad9)") (class "Default")
      (node (ref "MPU-9250") (pin "9") (pinfunction "9_9") (pintype "passive"))
    )
    (net (code "86") (name "unconnected-(MPU-9250-Pad10)") (class "Default")
      (node (ref "MPU-9250") (pin "10") (pinfunction "10_10") (pintype "passive"))
    )
    (net (code "87") (name "unconnected-(P1-ID-Pad4)") (class "Default")
      (node (ref "P1") (pin "4") (pinfunction "ID_4") (pintype "passive"))
    )
    (net (code "88") (name "unconnected-(U$1-CONFIG-Pad4)") (class "Default")
      (node (ref "U$1") (pin "4") (pinfunction "CONFIG_4") (pintype "bidirectional"))
    )
    (net (code "89") (name "unconnected-(U$1-VREF-Pad5)") (class "Default")
      (node (ref "U$1") (pin "5") (pinfunction "VREF_5") (pintype "bidirectional"))
    )
    (net (code "90") (name "unconnected-(U$2-NC-Pad17)") (class "Default")
      (node (ref "U$2") (pin "17") (pinfunction "NC_17") (pintype "bidirectional"))
    )
    (net (code "91") (name "unconnected-(U$2-NC2-Pad19)") (class "Default")
      (node (ref "U$2") (pin "19") (pinfunction "NC2_19") (pintype "bidirectional"))
    )
    (net (code "92") (name "unconnected-(U$2-RTCK\\-Pad11)") (class "Default")
      (node (ref "U$2") (pin "11") (pinfunction "RTCK\\_11") (pintype "bidirectional"))
    )
    (net (code "93") (name "unconnected-(U$3-CONFIG-Pad4)") (class "Default")
      (node (ref "U$3") (pin "4") (pinfunction "CONFIG_4") (pintype "bidirectional"))
    )
    (net (code "94") (name "unconnected-(U$3-VREF-Pad5)") (class "Default")
      (node (ref "U$3") (pin "5") (pinfunction "VREF_5") (pintype "bidirectional"))
    )
    (net (code "95") (name "unconnected-(U$4-PA7-Pad23)") (class "Default")
      (node (ref "U$4") (pin "23") (pinfunction "PA7_23") (pintype "bidirectional"))
    )
    (net (code "96") (name "unconnected-(U$4-PA8-Pad41)") (class "Default")
      (node (ref "U$4") (pin "41") (pinfunction "PA8_41") (pintype "bidirectional"))
    )
    (net (code "97") (name "unconnected-(U$4-PA9-Pad42)") (class "Default")
      (node (ref "U$4") (pin "42") (pinfunction "PA9_42") (pintype "bidirectional"))
    )
    (net (code "98") (name "unconnected-(U$4-PA10-Pad43)") (class "Default")
      (node (ref "U$4") (pin "43") (pinfunction "PA10_43") (pintype "bidirectional"))
    )
    (net (code "99") (name "unconnected-(U$4-PB2-Pad28)") (class "Default")
      (node (ref "U$4") (pin "28") (pinfunction "PB2_28") (pintype "bidirectional"))
    )
    (net (code "100") (name "unconnected-(U$4-PB6-Pad58)") (class "Default")
      (node (ref "U$4") (pin "58") (pinfunction "PB6_58") (pintype "bidirectional"))
    )
    (net (code "101") (name "unconnected-(U$4-PB7-Pad59)") (class "Default")
      (node (ref "U$4") (pin "59") (pinfunction "PB7_59") (pintype "bidirectional"))
    )
    (net (code "102") (name "unconnected-(U$4-PB12-Pad33)") (class "Default")
      (node (ref "U$4") (pin "33") (pinfunction "PB12_33") (pintype "bidirectional"))
    )
    (net (code "103") (name "unconnected-(U$4-PB13-Pad34)") (class "Default")
      (node (ref "U$4") (pin "34") (pinfunction "PB13_34") (pintype "bidirectional"))
    )
    (net (code "104") (name "unconnected-(U$4-PB14-Pad35)") (class "Default")
      (node (ref "U$4") (pin "35") (pinfunction "PB14_35") (pintype "bidirectional"))
    )
    (net (code "105") (name "unconnected-(U$4-PB15-Pad36)") (class "Default")
      (node (ref "U$4") (pin "36") (pinfunction "PB15_36") (pintype "bidirectional"))
    )
    (net (code "106") (name "unconnected-(U$4-PC7-Pad38)") (class "Default")
      (node (ref "U$4") (pin "38") (pinfunction "PC7_38") (pintype "bidirectional"))
    )
    (net (code "107") (name "unconnected-(U$4-PC8-Pad39)") (class "Default")
      (node (ref "U$4") (pin "39") (pinfunction "PC8_39") (pintype "bidirectional"))
    )
    (net (code "108") (name "unconnected-(U$4-PD2-Pad54)") (class "Default")
      (node (ref "U$4") (pin "54") (pinfunction "PD2_54") (pintype "bidirectional"))
    )
  )
)
